# SOL_R1.net
KiCad netlist of a schematic drawn in EAGLE
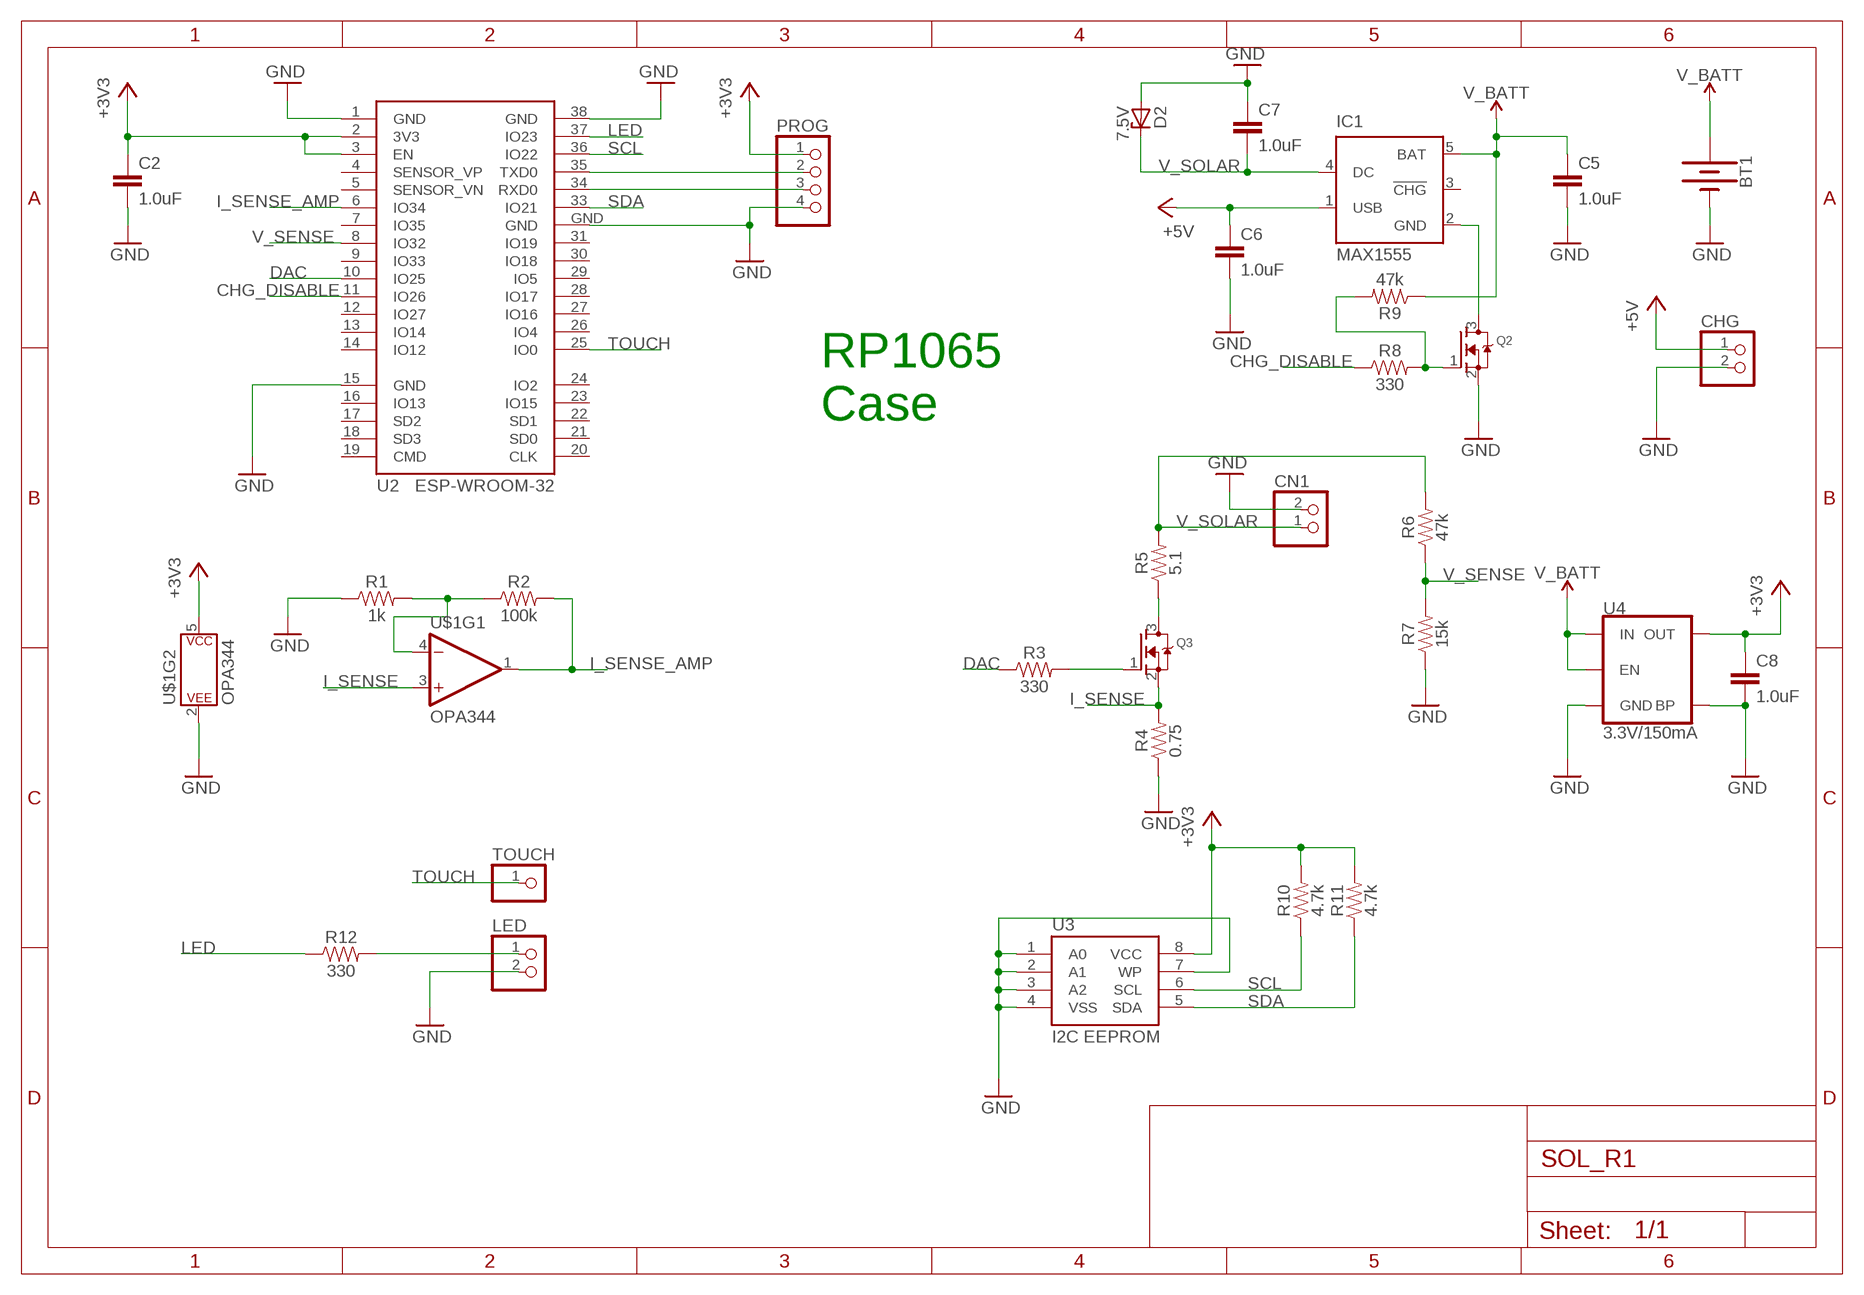
[diagram p0: schematic, sheet 1]

(export (version "E")
  (design (tool "Eeschema 10.0.6"))
  (components
    (comp (ref "BT1")
      (value "BATTERY-18650")
      (footprint "eagle-import:BATTERY_18650-HOLDER")
      (libsource (lib "eagle-import") (part "BATTERY-18650"))
    )
    (comp (ref "C2")
      (value "1.0uF")
      (footprint "eagle-import:0805")
      (libsource (lib "eagle-import") (part "1.0UF-0805-25V-10%"))
    )
    (comp (ref "C5")
      (value "1.0uF")
      (footprint "eagle-import:0805")
      (libsource (lib "eagle-import") (part "1.0UF-0805-25V-10%"))
    )
    (comp (ref "C6")
      (value "1.0uF")
      (footprint "eagle-import:0805")
      (libsource (lib "eagle-import") (part "1.0UF-0805-25V-10%"))
    )
    (comp (ref "C7")
      (value "1.0uF")
      (footprint "eagle-import:0805")
      (libsource (lib "eagle-import") (part "1.0UF-0805-25V-10%"))
    )
    (comp (ref "C8")
      (value "1.0uF")
      (footprint "eagle-import:0805")
      (libsource (lib "eagle-import") (part "1.0UF-0805-25V-10%"))
    )
    (comp (ref "CHG")
      (value "PINHD-1X2")
      (footprint "eagle-import:1X02")
      (libsource (lib "eagle-import") (part "PINHD-1X2"))
    )
    (comp (ref "CN1")
      (value "JST_2PIN-THM-RA")
      (footprint "eagle-import:JST-PH-2-THM-RA")
      (libsource (lib "eagle-import") (part "JST_2PIN-THM-RA"))
    )
    (comp (ref "D2")
      (value "7.5V")
      (footprint "eagle-import:ZDIO-5")
      (libsource (lib "eagle-import") (part "ZENER-DIODEZD-5"))
    )
    (comp (ref "IC1")
      (value "MAX1555")
      (footprint "eagle-import:SOT23-5L")
      (fields (field (name "MF") "MAXIM") (field (name "MPN") "MAX1555EZK+T"))
      (libsource (lib "eagle-import") (part "MAX1555"))
    )
    (comp (ref "LED")
      (value "PINHD-1X2")
      (footprint "eagle-import:1X02")
      (libsource (lib "eagle-import") (part "PINHD-1X2"))
    )
    (comp (ref "PROG")
      (value "PINHD-1X4")
      (footprint "eagle-import:1X04")
      (libsource (lib "eagle-import") (part "PINHD-1X4"))
    )
    (comp (ref "Q2")
      (value "MOSFET-NREFLOW")
      (footprint "eagle-import:SOT23")
      (libsource (lib "eagle-import") (part "MOSFET-NREFLOW"))
    )
    (comp (ref "Q3")
      (value "MOSFET-NREFLOW")
      (footprint "eagle-import:SOT23")
      (libsource (lib "eagle-import") (part "MOSFET-NREFLOW"))
    )
    (comp (ref "R1")
      (value "1k")
      (footprint "eagle-import:0603")
      (libsource (lib "eagle-import") (part "2.2KOHM-0603-1/10W-1%"))
    )
    (comp (ref "R2")
      (value "100k")
      (footprint "eagle-import:0603")
      (libsource (lib "eagle-import") (part "2.2KOHM-0603-1/10W-1%"))
    )
    (comp (ref "R3")
      (value "330")
      (footprint "eagle-import:0603")
      (libsource (lib "eagle-import") (part "2.2KOHM-0603-1/10W-1%"))
    )
    (comp (ref "R4")
      (value "0.75")
      (footprint "eagle-import:0805")
      (libsource (lib "eagle-import") (part "0.3OHM-0805-1/8W-1%"))
    )
    (comp (ref "R5")
      (value "5.1")
      (footprint "eagle-import:0603")
      (libsource (lib "eagle-import") (part "33OHM-0603-1/10W-1%"))
    )
    (comp (ref "R6")
      (value "47k")
      (footprint "eagle-import:0603")
      (libsource (lib "eagle-import") (part "47KOHM-0603-1/10W-1%"))
    )
    (comp (ref "R7")
      (value "15k")
      (footprint "eagle-import:0603")
      (libsource (lib "eagle-import") (part "15KOHM-0603-1/10W-1%"))
    )
    (comp (ref "R8")
      (value "330")
      (footprint "eagle-import:0603")
      (libsource (lib "eagle-import") (part "2.2KOHM-0603-1/10W-1%"))
    )
    (comp (ref "R9")
      (value "47k")
      (footprint "eagle-import:0603")
      (libsource (lib "eagle-import") (part "47KOHM-0603-1/10W-1%"))
    )
    (comp (ref "R10")
      (value "4.7k")
      (footprint "eagle-import:0603")
      (libsource (lib "eagle-import") (part "4.7KOHM-0603-1/10W-1%"))
    )
    (comp (ref "R11")
      (value "4.7k")
      (footprint "eagle-import:0603")
      (libsource (lib "eagle-import") (part "4.7KOHM-0603-1/10W-1%"))
    )
    (comp (ref "R12")
      (value "330")
      (footprint "eagle-import:0603")
      (libsource (lib "eagle-import") (part "2.2KOHM-0603-1/10W-1%"))
    )
    (comp (ref "TOUCH")
      (value "PINHD-1X1")
      (footprint "eagle-import:1X01")
      (libsource (lib "eagle-import") (part "PINHD-1X1"))
    )
    (comp (ref "U$1")
      (value "OPA344")
      (footprint "eagle-import:SOT23-5")
      (libsource (lib "eagle-import") (part "OPA344"))
    )
    (comp (ref "U2")
      (value "ESP-WROOM-32")
      (footprint "eagle-import:ESP-WROOM-32")
      (libsource (lib "eagle-import") (part "ESP-WROOM-32"))
    )
    (comp (ref "U3")
      (value "I2C EEPROM")
      (footprint "eagle-import:SO08-EIAJ")
      (libsource (lib "eagle-import") (part "EEPROM-I2CEIAJ"))
    )
    (comp (ref "U4")
      (value "3.3V/150mA")
      (footprint "eagle-import:SOT23-5")
      (libsource (lib "eagle-import") (part "V_REG_MIC52053.3V"))
    )
  )
  (nets
    (net (code "1") (name "+3V3") (class "Default")
      (node (ref "C2") (pin "1") (pinfunction "1_1") (pintype "passive"))
      (node (ref "C8") (pin "1") (pinfunction "1_1") (pintype "passive"))
      (node (ref "PROG") (pin "1") (pinfunction "1_1") (pintype "passive"))
      (node (ref "R10") (pin "2") (pinfunction "2_2") (pintype "passive"))
      (node (ref "R11") (pin "2") (pinfunction "2_2") (pintype "passive"))
      (node (ref "U$1") (pin "5") (pinfunction "P$V+_5") (pintype "bidirectional"))
      (node (ref "U2") (pin "2") (pinfunction "3V3_2") (pintype "power_in"))
      (node (ref "U2") (pin "3") (pinfunction "EN_3") (pintype "input"))
      (node (ref "U3") (pin "8") (pinfunction "VCC_8") (pintype "power_in"))
      (node (ref "U4") (pin "5") (pinfunction "OUT_5") (pintype "passive"))
    )
    (net (code "2") (name "+5V") (class "Default")
      (node (ref "C6") (pin "1") (pinfunction "1_1") (pintype "passive"))
      (node (ref "CHG") (pin "1") (pinfunction "1_1") (pintype "passive"))
      (node (ref "IC1") (pin "1") (pinfunction "USB_1") (pintype "input"))
    )
    (net (code "3") (name "/CHG_DISABLE") (class "Default")
      (node (ref "R8") (pin "1") (pinfunction "1_1") (pintype "passive"))
      (node (ref "U2") (pin "11") (pinfunction "IO26_11") (pintype "bidirectional"))
    )
    (net (code "4") (name "/DAC") (class "Default")
      (node (ref "R3") (pin "1") (pinfunction "1_1") (pintype "passive"))
      (node (ref "U2") (pin "10") (pinfunction "IO25_10") (pintype "bidirectional"))
    )
    (net (code "5") (name "/I_SENSE") (class "Default")
      (node (ref "Q3") (pin "2") (pinfunction "S_2") (pintype "bidirectional"))
      (node (ref "R4") (pin "2") (pinfunction "2_2") (pintype "passive"))
      (node (ref "U$1") (pin "3") (pinfunction "+IN_3") (pintype "input"))
    )
    (net (code "6") (name "/I_SENSE_AMP") (class "Default")
      (node (ref "R2") (pin "2") (pinfunction "2_2") (pintype "passive"))
      (node (ref "U$1") (pin "1") (pinfunction "OUT_1") (pintype "output"))
      (node (ref "U2") (pin "6") (pinfunction "IO34_6") (pintype "bidirectional"))
    )
    (net (code "7") (name "/LED") (class "Default")
      (node (ref "R12") (pin "1") (pinfunction "1_1") (pintype "passive"))
      (node (ref "U2") (pin "37") (pinfunction "IO23_37") (pintype "bidirectional"))
    )
    (net (code "8") (name "/SCL") (class "Default")
      (node (ref "R10") (pin "1") (pinfunction "1_1") (pintype "passive"))
      (node (ref "U2") (pin "36") (pinfunction "IO22_36") (pintype "bidirectional"))
      (node (ref "U3") (pin "6") (pinfunction "SCL_6") (pintype "bidirectional"))
    )
    (net (code "9") (name "/SDA") (class "Default")
      (node (ref "R11") (pin "1") (pinfunction "1_1") (pintype "passive"))
      (node (ref "U2") (pin "33") (pinfunction "IO21_33") (pintype "bidirectional"))
      (node (ref "U3") (pin "5") (pinfunction "SDA_5") (pintype "bidirectional"))
    )
    (net (code "10") (name "/TOUCH") (class "Default")
      (node (ref "TOUCH") (pin "1") (pinfunction "1_1") (pintype "passive"))
      (node (ref "U2") (pin "25") (pinfunction "IO0_25") (pintype "bidirectional"))
    )
    (net (code "11") (name "/V_SENSE") (class "Default")
      (node (ref "R6") (pin "1") (pinfunction "1_1") (pintype "passive"))
      (node (ref "R7") (pin "2") (pinfunction "2_2") (pintype "passive"))
      (node (ref "U2") (pin "8") (pinfunction "IO32_8") (pintype "bidirectional"))
    )
    (net (code "12") (name "/V_SOLAR") (class "Default")
      (node (ref "C7") (pin "2") (pinfunction "2_2") (pintype "passive"))
      (node (ref "CN1") (pin "1") (pinfunction "2_1") (pintype "passive"))
      (node (ref "D2") (pin "C") (pinfunction "C_C") (pintype "passive"))
      (node (ref "IC1") (pin "4") (pinfunction "DC_4") (pintype "input"))
      (node (ref "R5") (pin "2") (pinfunction "2_2") (pintype "passive"))
      (node (ref "R6") (pin "2") (pinfunction "2_2") (pintype "passive"))
    )
    (net (code "13") (name "GND") (class "Default")
      (node (ref "BT1") (pin "GND@1") (pinfunction "-_GND@1") (pintype "power_in"))
      (node (ref "C2") (pin "2") (pinfunction "2_2") (pintype "passive"))
      (node (ref "C5") (pin "2") (pinfunction "2_2") (pintype "passive"))
      (node (ref "C6") (pin "2") (pinfunction "2_2") (pintype "passive"))
      (node (ref "C7") (pin "1") (pinfunction "1_1") (pintype "passive"))
      (node (ref "C8") (pin "2") (pinfunction "2_2") (pintype "passive"))
      (node (ref "CHG") (pin "2") (pinfunction "2_2") (pintype "passive"))
      (node (ref "CN1") (pin "2") (pinfunction "1_2") (pintype "passive"))
      (node (ref "D2") (pin "A") (pinfunction "A_A") (pintype "passive"))
      (node (ref "LED") (pin "2") (pinfunction "2_2") (pintype "passive"))
      (node (ref "PROG") (pin "4") (pinfunction "4_4") (pintype "passive"))
      (node (ref "Q2") (pin "2") (pinfunction "S_2") (pintype "bidirectional"))
      (node (ref "R1") (pin "1") (pinfunction "1_1") (pintype "passive"))
      (node (ref "R4") (pin "1") (pinfunction "1_1") (pintype "passive"))
      (node (ref "R7") (pin "1") (pinfunction "1_1") (pintype "passive"))
      (node (ref "U$1") (pin "2") (pinfunction "P$V-_2") (pintype "bidirectional"))
      (node (ref "U2") (pin "1") (pinfunction "GND_1") (pintype "power_in"))
      (node (ref "U2") (pin "15") (pinfunction "GND_15") (pintype "power_in"))
      (node (ref "U2") (pin "38") (pinfunction "GND_38") (pintype "power_in"))
      (node (ref "U2") (pin "GND") (pinfunction "GND_GND") (pintype "power_in"))
      (node (ref "U3") (pin "1") (pinfunction "A0_1") (pintype "bidirectional"))
      (node (ref "U3") (pin "2") (pinfunction "A1_2") (pintype "bidirectional"))
      (node (ref "U3") (pin "3") (pinfunction "A2_3") (pintype "bidirectional"))
      (node (ref "U3") (pin "4") (pinfunction "VSS_4") (pintype "power_in"))
      (node (ref "U3") (pin "7") (pinfunction "WP_7") (pintype "bidirectional"))
      (node (ref "U4") (pin "2") (pinfunction "GND_2") (pintype "input"))
      (node (ref "U4") (pin "4") (pinfunction "BP_4") (pintype "input"))
    )
    (net (code "14") (name "Net-(IC1-GND)") (class "Default")
      (node (ref "IC1") (pin "2") (pinfunction "GND_2") (pintype "power_in"))
      (node (ref "Q2") (pin "3") (pinfunction "D_3") (pintype "bidirectional"))
    )
    (net (code "15") (name "Net-(LED-Pad1)") (class "Default")
      (node (ref "LED") (pin "1") (pinfunction "1_1") (pintype "passive"))
      (node (ref "R12") (pin "2") (pinfunction "2_2") (pintype "passive"))
    )
    (net (code "16") (name "Net-(Q2-G)") (class "Default")
      (node (ref "Q2") (pin "1") (pinfunction "G_1") (pintype "bidirectional"))
      (node (ref "R8") (pin "2") (pinfunction "2_2") (pintype "passive"))
      (node (ref "R9") (pin "2") (pinfunction "2_2") (pintype "passive"))
    )
    (net (code "17") (name "Net-(Q3-D)") (class "Default")
      (node (ref "Q3") (pin "3") (pinfunction "D_3") (pintype "bidirectional"))
      (node (ref "R5") (pin "1") (pinfunction "1_1") (pintype "passive"))
    )
    (net (code "18") (name "Net-(Q3-G)") (class "Default")
      (node (ref "Q3") (pin "1") (pinfunction "G_1") (pintype "bidirectional"))
      (node (ref "R3") (pin "2") (pinfunction "2_2") (pintype "passive"))
    )
    (net (code "19") (name "Net-(U$1A--IN)") (class "Default")
      (node (ref "R1") (pin "2") (pinfunction "2_2") (pintype "passive"))
      (node (ref "R2") (pin "1") (pinfunction "1_1") (pintype "passive"))
      (node (ref "U$1") (pin "4") (pinfunction "-IN_4") (pintype "input"))
    )
    (net (code "20") (name "Net-(U2-RXD0)") (class "Default")
      (node (ref "PROG") (pin "3") (pinfunction "3_3") (pintype "passive"))
      (node (ref "U2") (pin "34") (pinfunction "RXD0_34") (pintype "bidirectional"))
    )
    (net (code "21") (name "Net-(U2-TXD0)") (class "Default")
      (node (ref "PROG") (pin "2") (pinfunction "2_2") (pintype "passive"))
      (node (ref "U2") (pin "35") (pinfunction "TXD0_35") (pintype "bidirectional"))
    )
    (net (code "22") (name "V_BATT") (class "Default")
      (node (ref "BT1") (pin "PWR@1") (pinfunction "+_PWR@1") (pintype "power_in"))
      (node (ref "C5") (pin "1") (pinfunction "1_1") (pintype "passive"))
      (node (ref "IC1") (pin "5") (pinfunction "BAT_5") (pintype "passive"))
      (node (ref "R9") (pin "1") (pinfunction "1_1") (pintype "passive"))
      (node (ref "U4") (pin "1") (pinfunction "IN_1") (pintype "input"))
      (node (ref "U4") (pin "3") (pinfunction "EN_3") (pintype "input"))
    )
    (net (code "23") (name "unconnected-(IC1-~{CHG}-Pad3)") (class "Default")
      (node (ref "IC1") (pin "3") (pinfunction "~{CHG}_3") (pintype "output"))
    )
    (net (code "24") (name "unconnected-(U2-CLK-Pad20)") (class "Default")
      (node (ref "U2") (pin "20") (pinfunction "CLK_20") (pintype "bidirectional"))
    )
    (net (code "25") (name "unconnected-(U2-CMD-Pad19)") (class "Default")
      (node (ref "U2") (pin "19") (pinfunction "CMD_19") (pintype "bidirectional"))
    )
    (net (code "26") (name "unconnected-(U2-IO2-Pad24)") (class "Default")
      (node (ref "U2") (pin "24") (pinfunction "IO2_24") (pintype "bidirectional"))
    )
    (net (code "27") (name "unconnected-(U2-IO4-Pad26)") (class "Default")
      (node (ref "U2") (pin "26") (pinfunction "IO4_26") (pintype "bidirectional"))
    )
    (net (code "28") (name "unconnected-(U2-IO5-Pad29)") (class "Default")
      (node (ref "U2") (pin "29") (pinfunction "IO5_29") (pintype "bidirectional"))
    )
    (net (code "29") (name "unconnected-(U2-IO12-Pad14)") (class "Default")
      (node (ref "U2") (pin "14") (pinfunction "IO12_14") (pintype "bidirectional"))
    )
    (net (code "30") (name "unconnected-(U2-IO13-Pad16)") (class "Default")
      (node (ref "U2") (pin "16") (pinfunction "IO13_16") (pintype "bidirectional"))
    )
    (net (code "31") (name "unconnected-(U2-IO14-Pad13)") (class "Default")
      (node (ref "U2") (pin "13") (pinfunction "IO14_13") (pintype "bidirectional"))
    )
    (net (code "32") (name "unconnected-(U2-IO15-Pad23)") (class "Default")
      (node (ref "U2") (pin "23") (pinfunction "IO15_23") (pintype "bidirectional"))
    )
    (net (code "33") (name "unconnected-(U2-IO16-Pad27)") (class "Default")
      (node (ref "U2") (pin "27") (pinfunction "IO16_27") (pintype "bidirectional"))
    )
    (net (code "34") (name "unconnected-(U2-IO17-Pad28)") (class "Default")
      (node (ref "U2") (pin "28") (pinfunction "IO17_28") (pintype "bidirectional"))
    )
    (net (code "35") (name "unconnected-(U2-IO18-Pad30)") (class "Default")
      (node (ref "U2") (pin "30") (pinfunction "IO18_30") (pintype "bidirectional"))
    )
    (net (code "36") (name "unconnected-(U2-IO19-Pad31)") (class "Default")
      (node (ref "U2") (pin "31") (pinfunction "IO19_31") (pintype "bidirectional"))
    )
    (net (code "37") (name "unconnected-(U2-IO27-Pad12)") (class "Default")
      (node (ref "U2") (pin "12") (pinfunction "IO27_12") (pintype "bidirectional"))
    )
    (net (code "38") (name "unconnected-(U2-IO33-Pad9)") (class "Default")
      (node (ref "U2") (pin "9") (pinfunction "IO33_9") (pintype "bidirectional"))
    )
    (net (code "39") (name "unconnected-(U2-IO35-Pad7)") (class "Default")
      (node (ref "U2") (pin "7") (pinfunction "IO35_7") (pintype "bidirectional"))
    )
    (net (code "40") (name "unconnected-(U2-SD0-Pad21)") (class "Default")
      (node (ref "U2") (pin "21") (pinfunction "SD0_21") (pintype "bidirectional"))
    )
    (net (code "41") (name "unconnected-(U2-SD1-Pad22)") (class "Default")
      (node (ref "U2") (pin "22") (pinfunction "SD1_22") (pintype "bidirectional"))
    )
    (net (code "42") (name "unconnected-(U2-SD2-Pad17)") (class "Default")
      (node (ref "U2") (pin "17") (pinfunction "SD2_17") (pintype "bidirectional"))
    )
    (net (code "43") (name "unconnected-(U2-SD3-Pad18)") (class "Default")
      (node (ref "U2") (pin "18") (pinfunction "SD3_18") (pintype "bidirectional"))
    )
    (net (code "44") (name "unconnected-(U2-SENSOR_VN-Pad5)") (class "Default")
      (node (ref "U2") (pin "5") (pinfunction "SENSOR_VN_5") (pintype "bidirectional"))
    )
    (net (code "45") (name "unconnected-(U2-SENSOR_VP-Pad4)") (class "Default")
      (node (ref "U2") (pin "4") (pinfunction "SENSOR_VP_4") (pintype "bidirectional"))
    )
  )
)
